# PowerConnector.net
KiCad netlist of a schematic drawn in Altium Designer
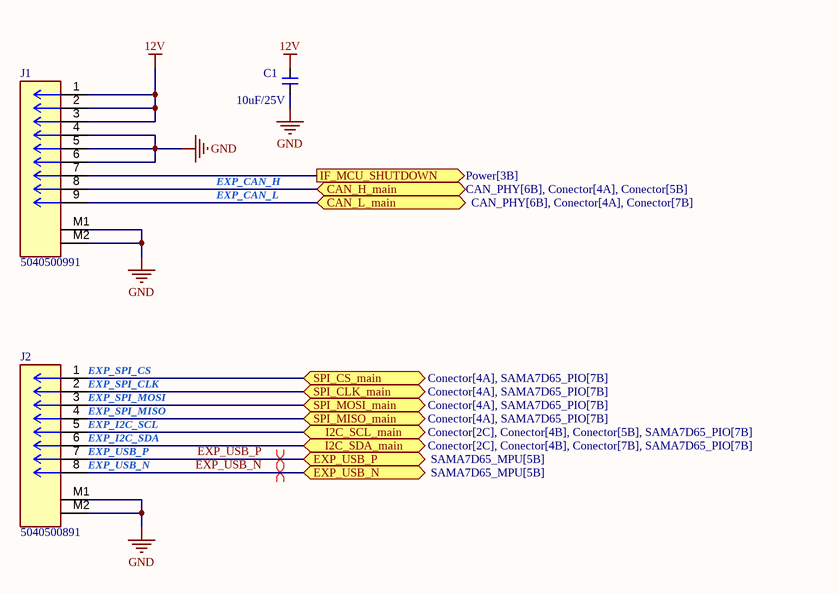
[diagram p0: PowerConnector.SchDoc]

(export (version "E")
  (design (tool "Eeschema 10.0.6"))
  (components
    (comp (ref "C1")
      (value "10uF/25V")
      (footprint "CAP_C_1005X60")
      (description "CAP CHIP")
      (libsource (lib "IFBschelib") (part "_CAP_C_2"))
    )
    (comp (ref "J1")
      (value "5040500991")
      (footprint "MOLEX_5040500991")
      (description "Connector Header Surface Mount, Right Angle 9 position 0.059\" (1.50mm)")
      (libsource (lib "IFBschelib") (part "5040500991"))
    )
    (comp (ref "J2")
      (value "5040500891")
      (footprint "MOLEX_5040500891")
      (description "Connector Header Surface Mount, Right Angle 8 position 0.059\" (1.50mm)`")
      (libsource (lib "IFBschelib") (part "5040500891"))
    )
  )
  (nets
    (net (code "1") (name "/CAN_H_main") (class "Default")
      (node (ref "J1") (pin "8") (pinfunction "8_8") (pintype "passive"))
    )
    (net (code "2") (name "/CAN_L_main") (class "Default")
      (node (ref "J1") (pin "9") (pinfunction "9_9") (pintype "passive"))
    )
    (net (code "3") (name "/EXP_USB_N") (class "Default")
      (node (ref "J2") (pin "8") (pinfunction "8_8") (pintype "passive"))
    )
    (net (code "4") (name "/EXP_USB_P") (class "Default")
      (node (ref "J2") (pin "7") (pinfunction "7_7") (pintype "passive"))
    )
    (net (code "5") (name "/I2C_SCL_main") (class "Default")
      (node (ref "J2") (pin "5") (pinfunction "5_5") (pintype "passive"))
    )
    (net (code "6") (name "/I2C_SDA_main") (class "Default")
      (node (ref "J2") (pin "6") (pinfunction "6_6") (pintype "passive"))
    )
    (net (code "7") (name "/IF_MCU_SHUTDOWN") (class "Default")
      (node (ref "J1") (pin "7") (pinfunction "7_7") (pintype "passive"))
    )
    (net (code "8") (name "/SPI_CLK_main") (class "Default")
      (node (ref "J2") (pin "2") (pinfunction "2_2") (pintype "passive"))
    )
    (net (code "9") (name "/SPI_CS_main") (class "Default")
      (node (ref "J2") (pin "1") (pinfunction "1_1") (pintype "passive"))
    )
    (net (code "10") (name "/SPI_MISO_main") (class "Default")
      (node (ref "J2") (pin "4") (pinfunction "4_4") (pintype "passive"))
    )
    (net (code "11") (name "/SPI_MOSI_main") (class "Default")
      (node (ref "J2") (pin "3") (pinfunction "3_3") (pintype "passive"))
    )
    (net (code "12") (name "12V") (class "Default")
      (node (ref "C1") (pin "2") (pinfunction "2_2") (pintype "passive"))
      (node (ref "J1") (pin "1") (pinfunction "1_1") (pintype "passive"))
      (node (ref "J1") (pin "2") (pinfunction "2_2") (pintype "passive"))
      (node (ref "J1") (pin "3") (pinfunction "3_3") (pintype "passive"))
    )
    (net (code "13") (name "GND") (class "Default")
      (node (ref "C1") (pin "1") (pinfunction "1_1") (pintype "passive"))
      (node (ref "J1") (pin "4") (pinfunction "4_4") (pintype "passive"))
      (node (ref "J1") (pin "5") (pinfunction "5_5") (pintype "passive"))
      (node (ref "J1") (pin "6") (pinfunction "6_6") (pintype "passive"))
      (node (ref "J1") (pin "M1") (pinfunction "M1_M1") (pintype "passive"))
      (node (ref "J1") (pin "M2") (pinfunction "M2_M2") (pintype "passive"))
      (node (ref "J2") (pin "M1") (pinfunction "M1_M1") (pintype "passive"))
      (node (ref "J2") (pin "M2") (pinfunction "M2_M2") (pintype "passive"))
    )
  )
)
